# WirelessTransceiverUSB_Rev-.net
KiCad netlist of a schematic drawn in EAGLE
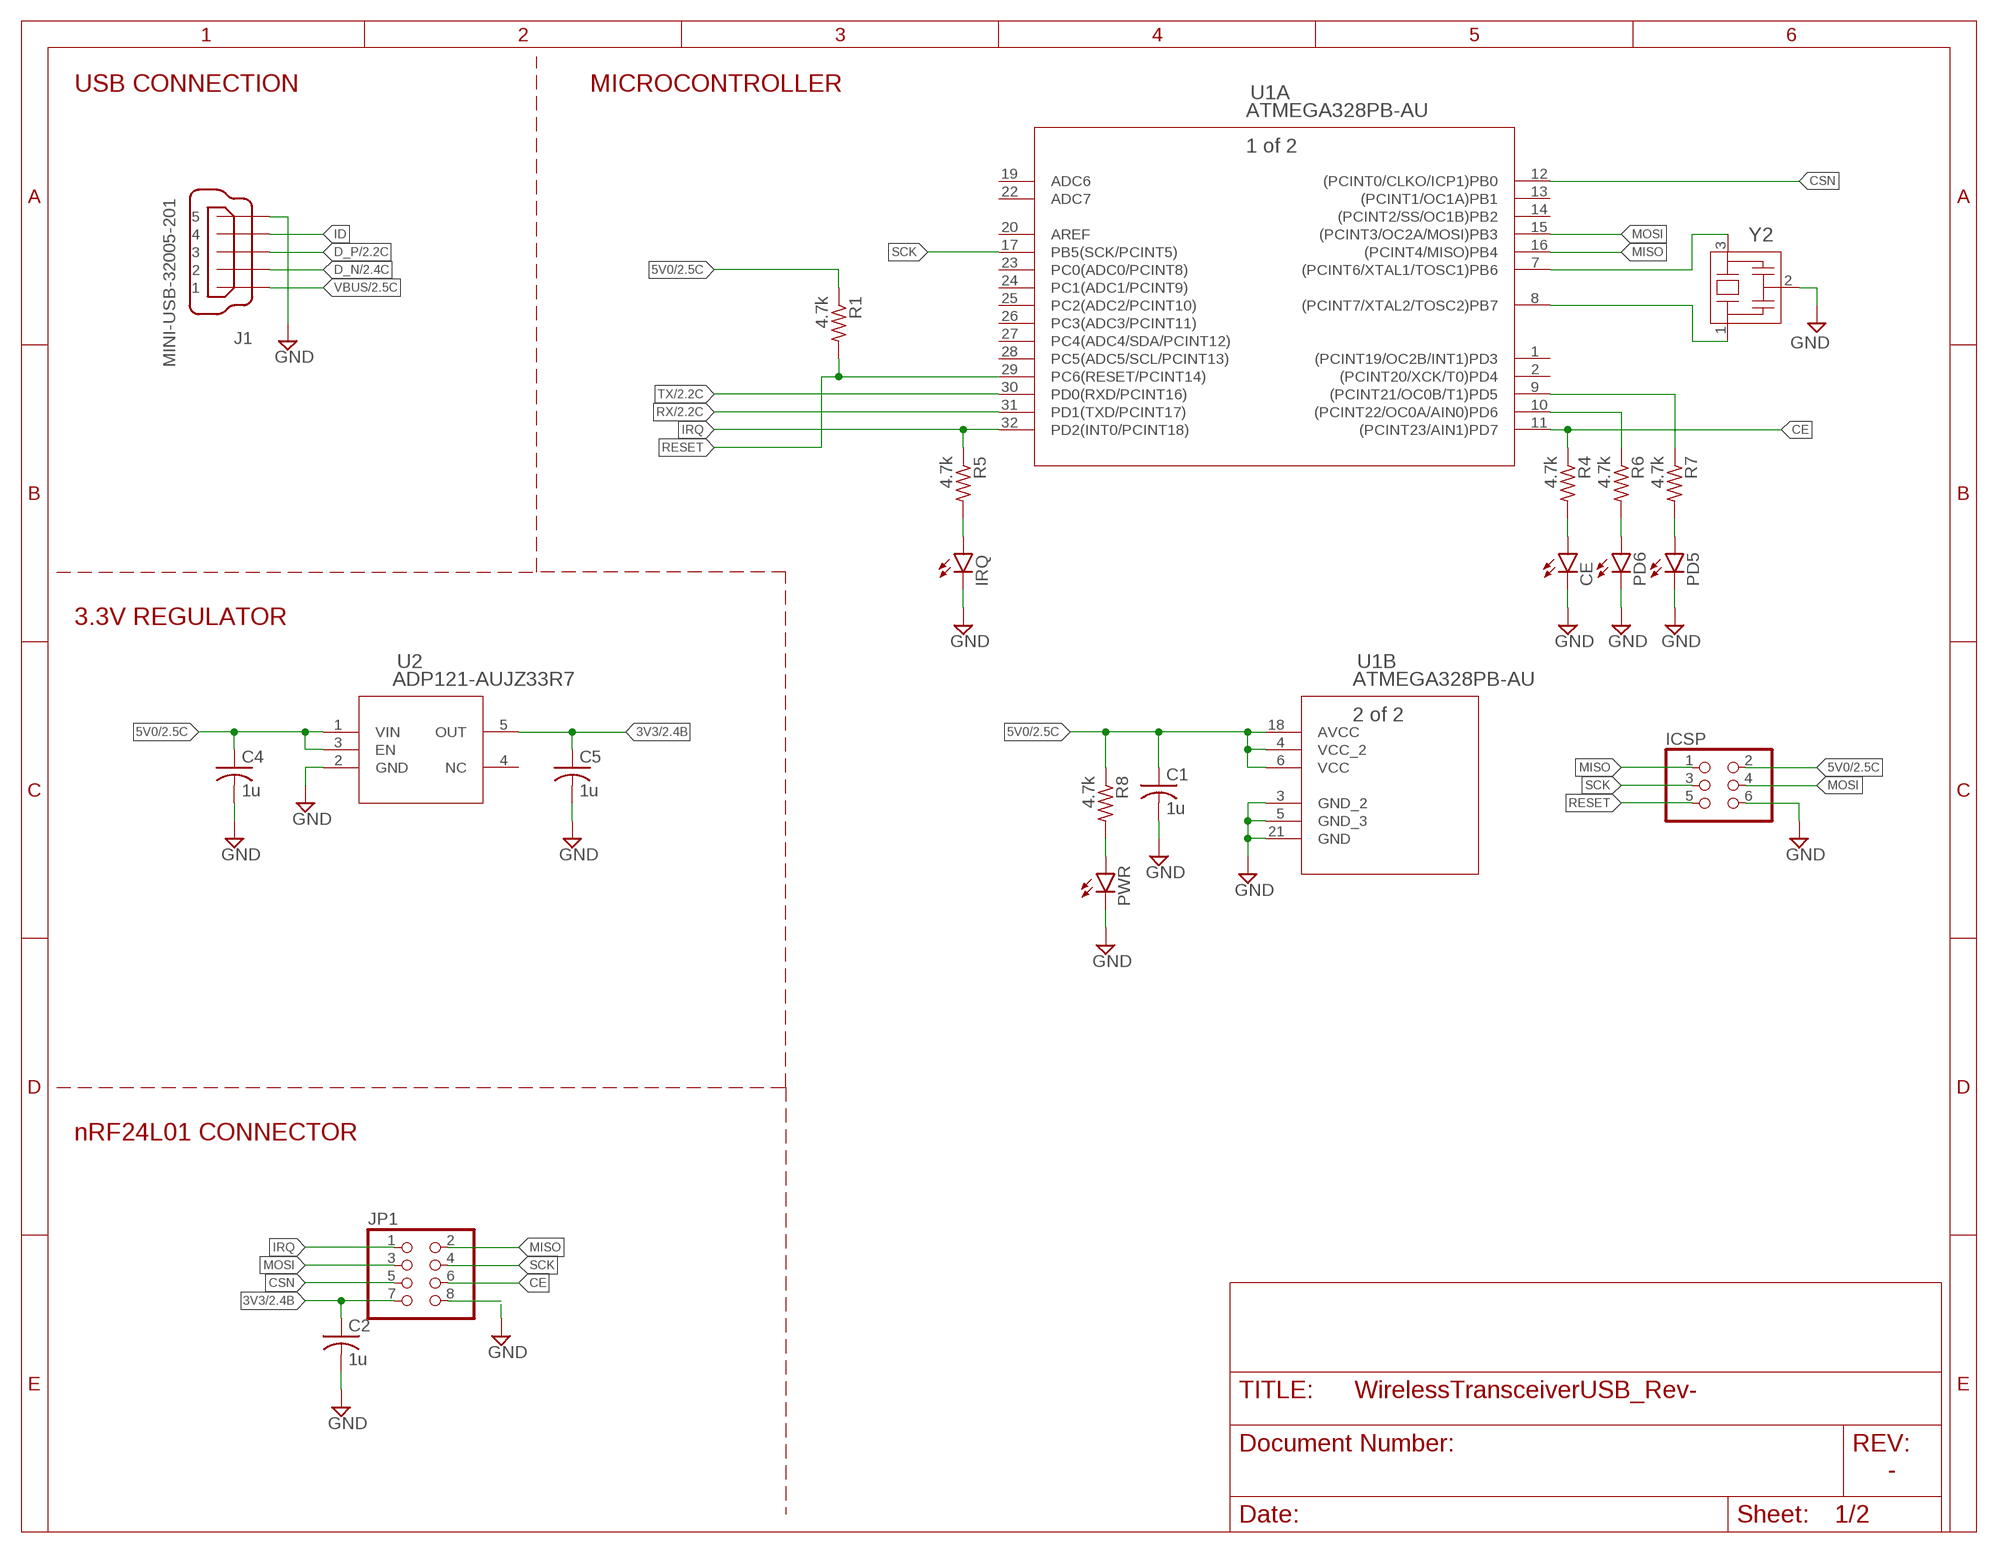
[diagram p0: schematic, sheet 1]
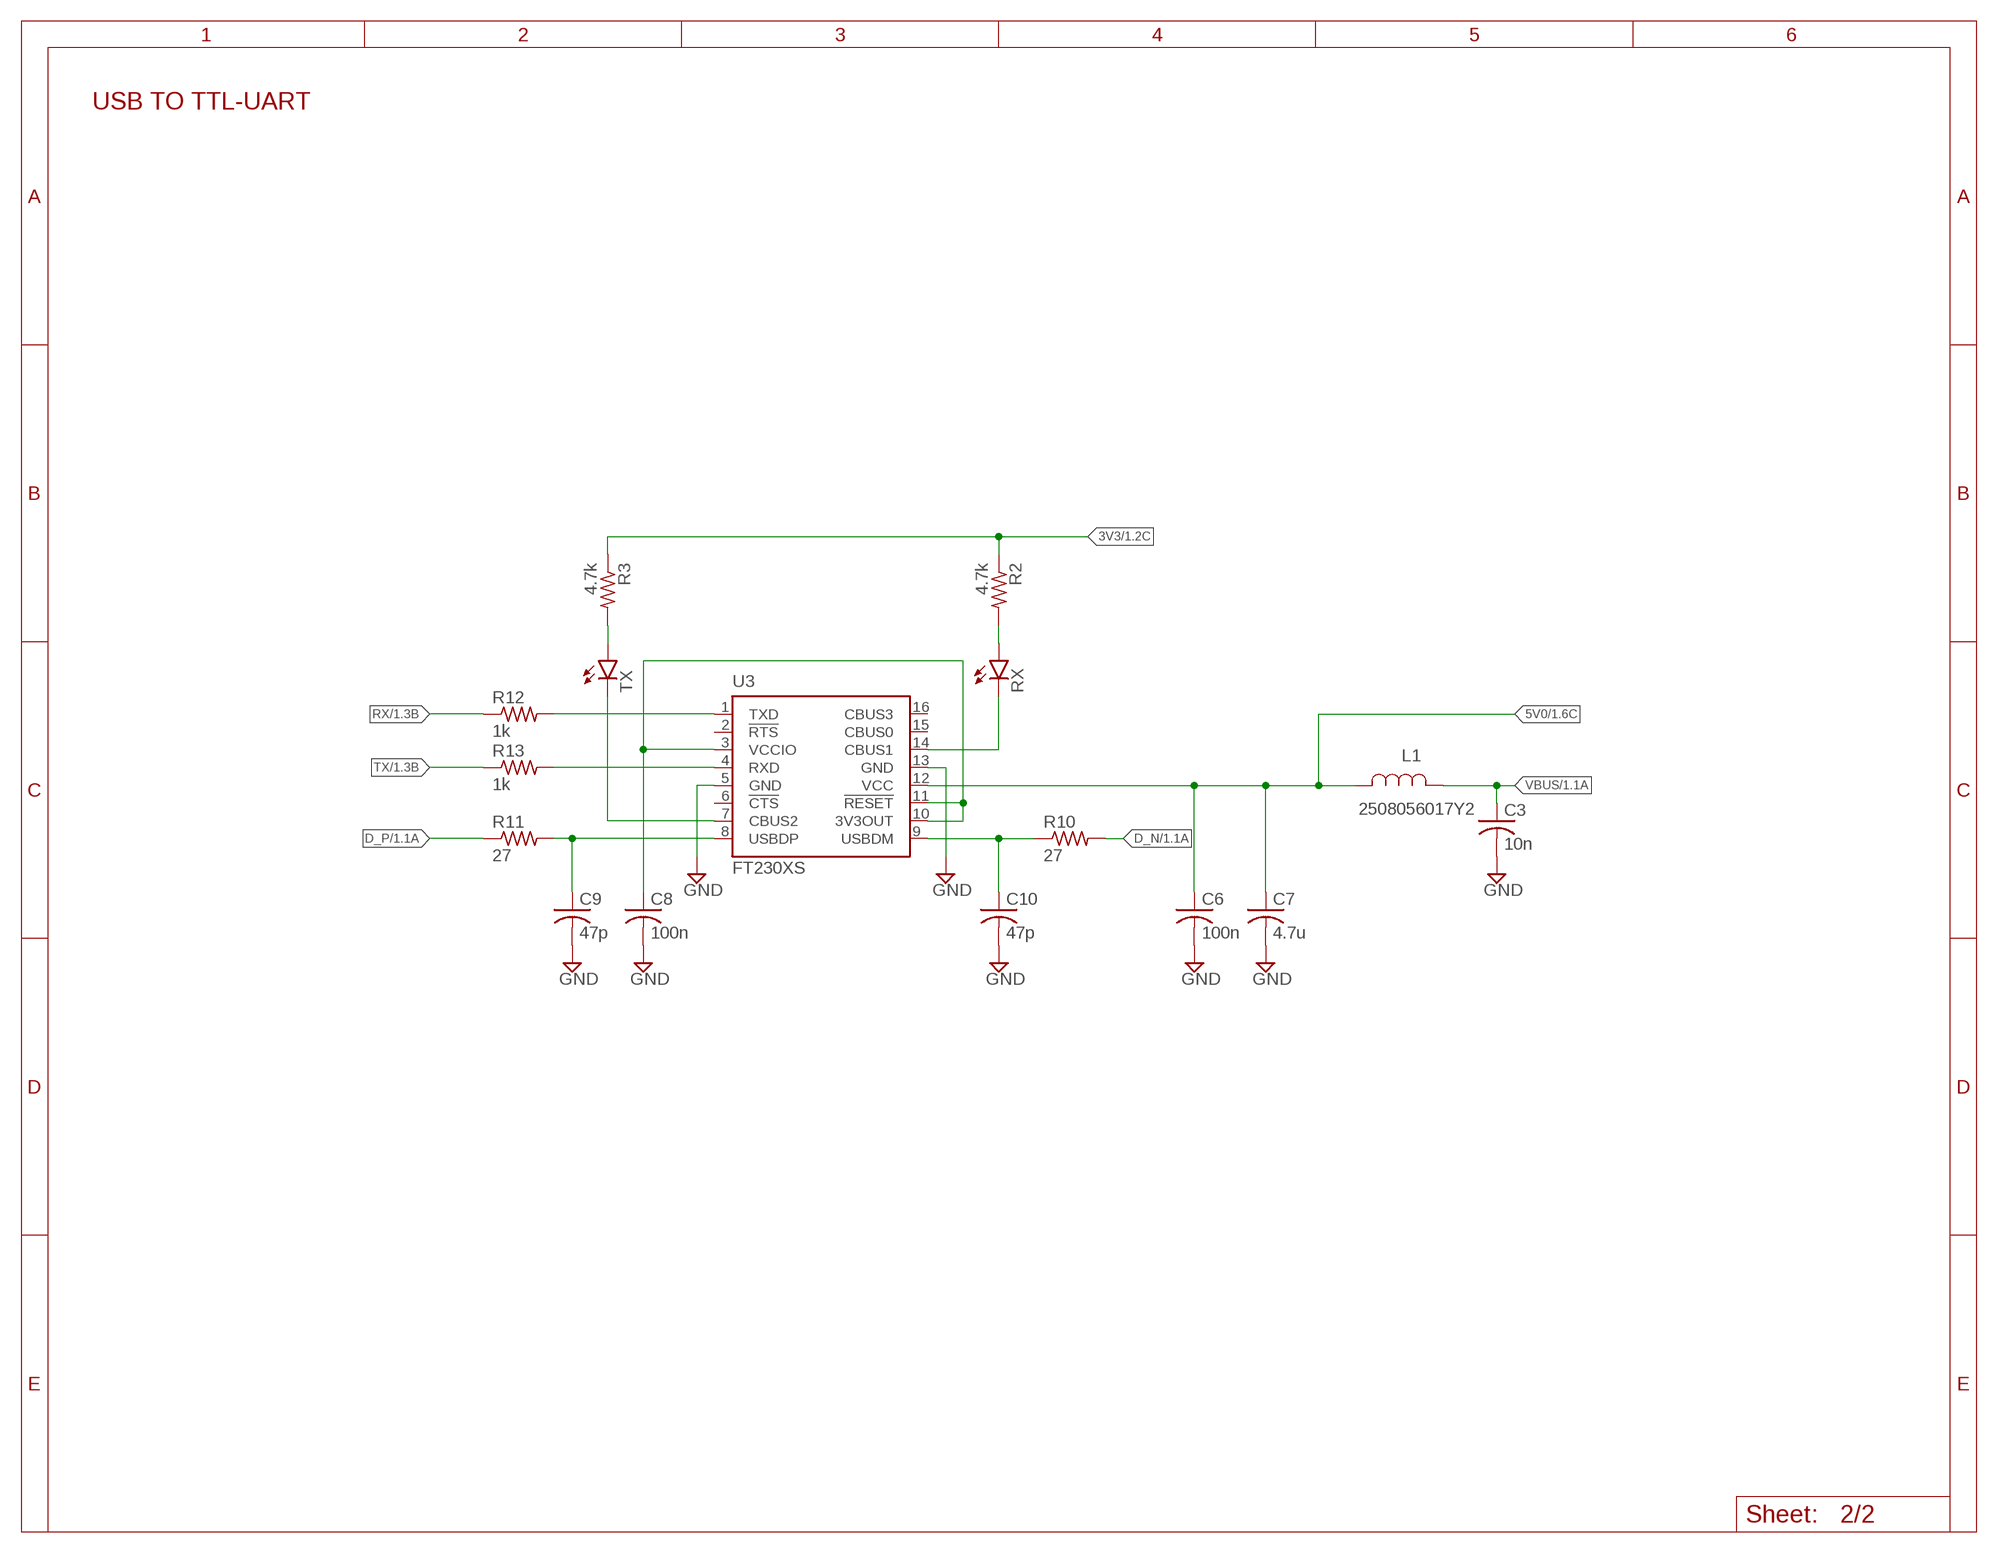
[diagram p1: schematic, sheet 2]

(export (version "E")
  (design (tool "Eeschema 10.0.6"))
  (components
    (comp (ref "C1")
      (value "1u")
      (footprint "eagle-import:C0805")
      (libsource (lib "eagle-import") (part "C-USC0805"))
    )
    (comp (ref "C2")
      (value "1u")
      (footprint "eagle-import:C0805")
      (libsource (lib "eagle-import") (part "C-USC0805"))
    )
    (comp (ref "C4")
      (value "1u")
      (footprint "eagle-import:C0805")
      (libsource (lib "eagle-import") (part "C-USC0805"))
    )
    (comp (ref "C5")
      (value "1u")
      (footprint "eagle-import:C0805")
      (libsource (lib "eagle-import") (part "C-USC0805"))
    )
    (comp (ref "CE")
      (value "LEDSML0805")
      (footprint "eagle-import:SML0805")
      (libsource (lib "eagle-import") (part "LEDSML0805"))
    )
    (comp (ref "ICSP")
      (value "PINHD-2X3")
      (footprint "eagle-import:2X03")
      (libsource (lib "eagle-import") (part "PINHD-2X3"))
    )
    (comp (ref "IRQ")
      (value "LEDSML0805")
      (footprint "eagle-import:SML0805")
      (libsource (lib "eagle-import") (part "LEDSML0805"))
    )
    (comp (ref "J1")
      (value "MINI-USB-32005-201")
      (footprint "eagle-import:32005-201")
      (libsource (lib "eagle-import") (part "MINI-USB-32005-201"))
    )
    (comp (ref "JP1")
      (value "PINHD-2X4")
      (footprint "eagle-import:2X04")
      (libsource (lib "eagle-import") (part "PINHD-2X4"))
    )
    (comp (ref "PD5")
      (value "LEDSML0805")
      (footprint "eagle-import:SML0805")
      (libsource (lib "eagle-import") (part "LEDSML0805"))
    )
    (comp (ref "PD6")
      (value "LEDSML0805")
      (footprint "eagle-import:SML0805")
      (libsource (lib "eagle-import") (part "LEDSML0805"))
    )
    (comp (ref "PWR")
      (value "LEDSML0805")
      (footprint "eagle-import:SML0805")
      (libsource (lib "eagle-import") (part "LEDSML0805"))
    )
    (comp (ref "R1")
      (value "4.7k")
      (footprint "eagle-import:R0805")
      (libsource (lib "eagle-import") (part "R-US_R0805"))
    )
    (comp (ref "R4")
      (value "4.7k")
      (footprint "eagle-import:R0805")
      (libsource (lib "eagle-import") (part "R-US_R0805"))
    )
    (comp (ref "R5")
      (value "4.7k")
      (footprint "eagle-import:R0805")
      (libsource (lib "eagle-import") (part "R-US_R0805"))
    )
    (comp (ref "R6")
      (value "4.7k")
      (footprint "eagle-import:R0805")
      (libsource (lib "eagle-import") (part "R-US_R0805"))
    )
    (comp (ref "R7")
      (value "4.7k")
      (footprint "eagle-import:R0805")
      (libsource (lib "eagle-import") (part "R-US_R0805"))
    )
    (comp (ref "R8")
      (value "4.7k")
      (footprint "eagle-import:R0805")
      (libsource (lib "eagle-import") (part "R-US_R0805"))
    )
    (comp (ref "U1")
      (value "ATMEGA328PB-AU")
      (footprint "eagle-import:32A_MCH")
      (fields (field (name "COPYRIGHT") "Copyright (C) 2023 Ultra Librarian. All rights reserved."))
      (libsource (lib "eagle-import") (part "ATMEGA328PB-AU"))
    )
    (comp (ref "U2")
      (value "ADP121-AUJZ33R7")
      (footprint "eagle-import:UJ_5_ADI")
      (fields (field (name "COPYRIGHT") "Copyright (C) 2023 Ultra Librarian. All rights reserved."))
      (libsource (lib "eagle-import") (part "ADP121-AUJZ33R7"))
    )
    (comp (ref "Y2")
      (value "CSTNE16M0V530000R0")
      (footprint "eagle-import:CSTNE16M0V530000R0_MUR")
      (fields (field (name "COPYRIGHT") "Copyright (C) 2023 Ultra Librarian. All rights reserved."))
      (libsource (lib "eagle-import") (part "CSTNE16M0V530000R0"))
    )
    (comp (ref "C3")
      (value "10n")
      (footprint "eagle-import:C0805")
      (libsource (lib "eagle-import") (part "C-USC0805"))
    )
    (comp (ref "C6")
      (value "100n")
      (footprint "eagle-import:C0805")
      (libsource (lib "eagle-import") (part "C-USC0805"))
    )
    (comp (ref "C7")
      (value "4.7u")
      (footprint "eagle-import:C0805")
      (libsource (lib "eagle-import") (part "C-USC0805"))
    )
    (comp (ref "C8")
      (value "100n")
      (footprint "eagle-import:C0805")
      (libsource (lib "eagle-import") (part "C-USC0805"))
    )
    (comp (ref "C9")
      (value "47p")
      (footprint "eagle-import:C0603")
      (libsource (lib "eagle-import") (part "C-USC0603"))
    )
    (comp (ref "C10")
      (value "47p")
      (footprint "eagle-import:C0603")
      (libsource (lib "eagle-import") (part "C-USC0603"))
    )
    (comp (ref "L1")
      (value "2508056017Y2")
      (footprint "eagle-import:IND_25_0805_FRT")
      (fields (field (name "COPYRIGHT") "Copyright (C) 2023 Ultra Librarian. All rights reserved."))
      (libsource (lib "eagle-import") (part "2508056017Y2"))
    )
    (comp (ref "R2")
      (value "4.7k")
      (footprint "eagle-import:R0805")
      (libsource (lib "eagle-import") (part "R-US_R0805"))
    )
    (comp (ref "R3")
      (value "4.7k")
      (footprint "eagle-import:R0805")
      (libsource (lib "eagle-import") (part "R-US_R0805"))
    )
    (comp (ref "R10")
      (value "27")
      (footprint "eagle-import:R0603")
      (libsource (lib "eagle-import") (part "R-US_R0603"))
    )
    (comp (ref "R11")
      (value "27")
      (footprint "eagle-import:R0603")
      (libsource (lib "eagle-import") (part "R-US_R0603"))
    )
    (comp (ref "R12")
      (value "1k")
      (footprint "eagle-import:R0805")
      (libsource (lib "eagle-import") (part "R-US_R0805"))
    )
    (comp (ref "R13")
      (value "1k")
      (footprint "eagle-import:R0805")
      (libsource (lib "eagle-import") (part "R-US_R0805"))
    )
    (comp (ref "RX")
      (value "LEDSML0805")
      (footprint "eagle-import:SML0805")
      (libsource (lib "eagle-import") (part "LEDSML0805"))
    )
    (comp (ref "TX")
      (value "LEDSML0805")
      (footprint "eagle-import:SML0805")
      (libsource (lib "eagle-import") (part "LEDSML0805"))
    )
    (comp (ref "U3")
      (value "FT230XS")
      (footprint "eagle-import:SSOP16")
      (libsource (lib "eagle-import") (part "FT230XS"))
    )
  )
  (nets
    (net (code "1") (name "3V3") (class "Default")
      (node (ref "C2") (pin "1") (pinfunction "1_1") (pintype "passive"))
      (node (ref "C5") (pin "1") (pinfunction "1_1") (pintype "passive"))
      (node (ref "JP1") (pin "7") (pinfunction "7_7") (pintype "passive"))
      (node (ref "R2") (pin "1") (pinfunction "1_1") (pintype "passive"))
      (node (ref "R3") (pin "1") (pinfunction "1_1") (pintype "passive"))
      (node (ref "U2") (pin "5") (pinfunction "OUT_5") (pintype "output"))
    )
    (net (code "2") (name "5V0") (class "Default")
      (node (ref "C1") (pin "1") (pinfunction "1_1") (pintype "passive"))
      (node (ref "C4") (pin "1") (pinfunction "1_1") (pintype "passive"))
      (node (ref "C6") (pin "1") (pinfunction "1_1") (pintype "passive"))
      (node (ref "C7") (pin "1") (pinfunction "1_1") (pintype "passive"))
      (node (ref "ICSP") (pin "2") (pinfunction "2_2") (pintype "passive"))
      (node (ref "L1") (pin "2") (pinfunction "2_2") (pintype "passive"))
      (node (ref "R1") (pin "1") (pinfunction "1_1") (pintype "passive"))
      (node (ref "R8") (pin "1") (pinfunction "1_1") (pintype "passive"))
      (node (ref "U1") (pin "18") (pinfunction "AVCC_18") (pintype "power_in"))
      (node (ref "U1") (pin "4") (pinfunction "VCC_2_4") (pintype "power_in"))
      (node (ref "U1") (pin "6") (pinfunction "VCC_6") (pintype "power_in"))
      (node (ref "U2") (pin "1") (pinfunction "VIN_1") (pintype "input"))
      (node (ref "U2") (pin "3") (pinfunction "EN_3") (pintype "input"))
      (node (ref "U3") (pin "12") (pinfunction "VCC_12") (pintype "power_in"))
    )
    (net (code "3") (name "CE") (class "Default")
      (node (ref "JP1") (pin "6") (pinfunction "6_6") (pintype "passive"))
      (node (ref "R4") (pin "1") (pinfunction "1_1") (pintype "passive"))
      (node (ref "U1") (pin "11") (pinfunction "(PCINT23/AIN1)PD7_11") (pintype "bidirectional"))
    )
    (net (code "4") (name "CSN") (class "Default")
      (node (ref "JP1") (pin "5") (pinfunction "5_5") (pintype "passive"))
      (node (ref "U1") (pin "12") (pinfunction "(PCINT0/CLKO/ICP1)PB0_12") (pintype "bidirectional"))
    )
    (net (code "5") (name "D_N") (class "Default")
      (node (ref "J1") (pin "2") (pinfunction "2_2") (pintype "passive"))
      (node (ref "R10") (pin "2") (pinfunction "2_2") (pintype "passive"))
    )
    (net (code "6") (name "D_P") (class "Default")
      (node (ref "J1") (pin "3") (pinfunction "3_3") (pintype "passive"))
      (node (ref "R11") (pin "1") (pinfunction "1_1") (pintype "passive"))
    )
    (net (code "7") (name "GND") (class "Default")
      (node (ref "C1") (pin "2") (pinfunction "2_2") (pintype "passive"))
      (node (ref "C10") (pin "2") (pinfunction "2_2") (pintype "passive"))
      (node (ref "C2") (pin "2") (pinfunction "2_2") (pintype "passive"))
      (node (ref "C3") (pin "2") (pinfunction "2_2") (pintype "passive"))
      (node (ref "C4") (pin "2") (pinfunction "2_2") (pintype "passive"))
      (node (ref "C5") (pin "2") (pinfunction "2_2") (pintype "passive"))
      (node (ref "C6") (pin "2") (pinfunction "2_2") (pintype "passive"))
      (node (ref "C7") (pin "2") (pinfunction "2_2") (pintype "passive"))
      (node (ref "C8") (pin "2") (pinfunction "2_2") (pintype "passive"))
      (node (ref "C9") (pin "2") (pinfunction "2_2") (pintype "passive"))
      (node (ref "CE") (pin "C") (pinfunction "C_C") (pintype "passive"))
      (node (ref "ICSP") (pin "6") (pinfunction "6_6") (pintype "passive"))
      (node (ref "IRQ") (pin "C") (pinfunction "C_C") (pintype "passive"))
      (node (ref "J1") (pin "5") (pinfunction "5_5") (pintype "passive"))
      (node (ref "JP1") (pin "8") (pinfunction "8_8") (pintype "passive"))
      (node (ref "PD5") (pin "C") (pinfunction "C_C") (pintype "passive"))
      (node (ref "PD6") (pin "C") (pinfunction "C_C") (pintype "passive"))
      (node (ref "PWR") (pin "C") (pinfunction "C_C") (pintype "passive"))
      (node (ref "U1") (pin "21") (pinfunction "GND_21") (pintype "power_in"))
      (node (ref "U1") (pin "3") (pinfunction "GND_2_3") (pintype "power_in"))
      (node (ref "U1") (pin "5") (pinfunction "GND_3_5") (pintype "power_in"))
      (node (ref "U2") (pin "2") (pinfunction "GND_2") (pintype "power_in"))
      (node (ref "U3") (pin "13") (pinfunction "GND_13") (pintype "power_in"))
      (node (ref "U3") (pin "5") (pinfunction "GND_5") (pintype "power_in"))
      (node (ref "Y2") (pin "2") (pinfunction "2_2") (pintype "passive"))
    )
    (net (code "8") (name "ID") (class "Default")
      (node (ref "J1") (pin "4") (pinfunction "4_4") (pintype "passive"))
    )
    (net (code "9") (name "IRQ") (class "Default")
      (node (ref "JP1") (pin "1") (pinfunction "1_1") (pintype "passive"))
      (node (ref "R5") (pin "1") (pinfunction "1_1") (pintype "passive"))
      (node (ref "U1") (pin "32") (pinfunction "PD2(INT0/PCINT18)_32") (pintype "bidirectional"))
    )
    (net (code "10") (name "MISO") (class "Default")
      (node (ref "ICSP") (pin "1") (pinfunction "1_1") (pintype "passive"))
      (node (ref "JP1") (pin "2") (pinfunction "2_2") (pintype "passive"))
      (node (ref "U1") (pin "16") (pinfunction "(PCINT4/MISO)PB4_16") (pintype "bidirectional"))
    )
    (net (code "11") (name "MOSI") (class "Default")
      (node (ref "ICSP") (pin "4") (pinfunction "4_4") (pintype "passive"))
      (node (ref "JP1") (pin "3") (pinfunction "3_3") (pintype "passive"))
      (node (ref "U1") (pin "15") (pinfunction "(PCINT3/OC2A/MOSI)PB3_15") (pintype "bidirectional"))
    )
    (net (code "12") (name "Net-(CE-PadA)") (class "Default")
      (node (ref "CE") (pin "A") (pinfunction "A_A") (pintype "passive"))
      (node (ref "R4") (pin "2") (pinfunction "2_2") (pintype "passive"))
    )
    (net (code "13") (name "Net-(IRQ-PadA)") (class "Default")
      (node (ref "IRQ") (pin "A") (pinfunction "A_A") (pintype "passive"))
      (node (ref "R5") (pin "2") (pinfunction "2_2") (pintype "passive"))
    )
    (net (code "14") (name "Net-(PD5-PadA)") (class "Default")
      (node (ref "PD5") (pin "A") (pinfunction "A_A") (pintype "passive"))
      (node (ref "R7") (pin "2") (pinfunction "2_2") (pintype "passive"))
    )
    (net (code "15") (name "Net-(PD6-PadA)") (class "Default")
      (node (ref "PD6") (pin "A") (pinfunction "A_A") (pintype "passive"))
      (node (ref "R6") (pin "2") (pinfunction "2_2") (pintype "passive"))
    )
    (net (code "16") (name "Net-(PWR-PadA)") (class "Default")
      (node (ref "PWR") (pin "A") (pinfunction "A_A") (pintype "passive"))
      (node (ref "R8") (pin "2") (pinfunction "2_2") (pintype "passive"))
    )
    (net (code "17") (name "Net-(R2-Pad2)") (class "Default")
      (node (ref "R2") (pin "2") (pinfunction "2_2") (pintype "passive"))
      (node (ref "RX") (pin "A") (pinfunction "A_A") (pintype "passive"))
    )
    (net (code "18") (name "Net-(R3-Pad2)") (class "Default")
      (node (ref "R3") (pin "2") (pinfunction "2_2") (pintype "passive"))
      (node (ref "TX") (pin "A") (pinfunction "A_A") (pintype "passive"))
    )
    (net (code "19") (name "Net-(U1A-(PCINT6{slash}XTAL1{slash}TOSC1)PB6)") (class "Default")
      (node (ref "U1") (pin "7") (pinfunction "(PCINT6/XTAL1/TOSC1)PB6_7") (pintype "bidirectional"))
      (node (ref "Y2") (pin "3") (pinfunction "3_3") (pintype "output"))
    )
    (net (code "20") (name "Net-(U1A-(PCINT7{slash}XTAL2{slash}TOSC2)PB7)") (class "Default")
      (node (ref "U1") (pin "8") (pinfunction "(PCINT7/XTAL2/TOSC2)PB7_8") (pintype "bidirectional"))
      (node (ref "Y2") (pin "1") (pinfunction "1_1") (pintype "input"))
    )
    (net (code "21") (name "Net-(U1A-(PCINT21{slash}OC0B{slash}T1)PD5)") (class "Default")
      (node (ref "R7") (pin "1") (pinfunction "1_1") (pintype "passive"))
      (node (ref "U1") (pin "9") (pinfunction "(PCINT21/OC0B/T1)PD5_9") (pintype "bidirectional"))
    )
    (net (code "22") (name "Net-(U1A-(PCINT22{slash}OC0A{slash}AIN0)PD6)") (class "Default")
      (node (ref "R6") (pin "1") (pinfunction "1_1") (pintype "passive"))
      (node (ref "U1") (pin "10") (pinfunction "(PCINT22/OC0A/AIN0)PD6_10") (pintype "bidirectional"))
    )
    (net (code "23") (name "Net-(U3-3V3OUT)") (class "Default")
      (node (ref "C8") (pin "1") (pinfunction "1_1") (pintype "passive"))
      (node (ref "U3") (pin "10") (pinfunction "3V3OUT_10") (pintype "output"))
      (node (ref "U3") (pin "11") (pinfunction "~{RESET}_11") (pintype "input"))
      (node (ref "U3") (pin "3") (pinfunction "VCCIO_3") (pintype "power_in"))
    )
    (net (code "24") (name "Net-(U3-CBUS1)") (class "Default")
      (node (ref "RX") (pin "C") (pinfunction "C_C") (pintype "passive"))
      (node (ref "U3") (pin "14") (pinfunction "CBUS1_14") (pintype "bidirectional"))
    )
    (net (code "25") (name "Net-(U3-CBUS2)") (class "Default")
      (node (ref "TX") (pin "C") (pinfunction "C_C") (pintype "passive"))
      (node (ref "U3") (pin "7") (pinfunction "CBUS2_7") (pintype "bidirectional"))
    )
    (net (code "26") (name "Net-(U3-RXD)") (class "Default")
      (node (ref "R13") (pin "2") (pinfunction "2_2") (pintype "passive"))
      (node (ref "U3") (pin "4") (pinfunction "RXD_4") (pintype "input"))
    )
    (net (code "27") (name "Net-(U3-TXD)") (class "Default")
      (node (ref "R12") (pin "2") (pinfunction "2_2") (pintype "passive"))
      (node (ref "U3") (pin "1") (pinfunction "TXD_1") (pintype "output"))
    )
    (net (code "28") (name "Net-(U3-USBDM)") (class "Default")
      (node (ref "C10") (pin "1") (pinfunction "1_1") (pintype "passive"))
      (node (ref "R10") (pin "1") (pinfunction "1_1") (pintype "passive"))
      (node (ref "U3") (pin "9") (pinfunction "USBDM_9") (pintype "input"))
    )
    (net (code "29") (name "Net-(U3-USBDP)") (class "Default")
      (node (ref "C9") (pin "1") (pinfunction "1_1") (pintype "passive"))
      (node (ref "R11") (pin "2") (pinfunction "2_2") (pintype "passive"))
      (node (ref "U3") (pin "8") (pinfunction "USBDP_8") (pintype "input"))
    )
    (net (code "30") (name "RESET") (class "Default")
      (node (ref "ICSP") (pin "5") (pinfunction "5_5") (pintype "passive"))
      (node (ref "R1") (pin "2") (pinfunction "2_2") (pintype "passive"))
      (node (ref "U1") (pin "29") (pinfunction "PC6(RESET/PCINT14)_29") (pintype "bidirectional"))
    )
    (net (code "31") (name "RX") (class "Default")
      (node (ref "R12") (pin "1") (pinfunction "1_1") (pintype "passive"))
      (node (ref "U1") (pin "31") (pinfunction "PD1(TXD/PCINT17)_31") (pintype "bidirectional"))
    )
    (net (code "32") (name "SCK") (class "Default")
      (node (ref "ICSP") (pin "3") (pinfunction "3_3") (pintype "passive"))
      (node (ref "JP1") (pin "4") (pinfunction "4_4") (pintype "passive"))
      (node (ref "U1") (pin "17") (pinfunction "PB5(SCK/PCINT5)_17") (pintype "bidirectional"))
    )
    (net (code "33") (name "TX") (class "Default")
      (node (ref "R13") (pin "1") (pinfunction "1_1") (pintype "passive"))
      (node (ref "U1") (pin "30") (pinfunction "PD0(RXD/PCINT16)_30") (pintype "bidirectional"))
    )
    (net (code "34") (name "VBUS") (class "Default")
      (node (ref "C3") (pin "1") (pinfunction "1_1") (pintype "passive"))
      (node (ref "J1") (pin "1") (pinfunction "1_1") (pintype "passive"))
      (node (ref "L1") (pin "1") (pinfunction "1_1") (pintype "passive"))
    )
    (net (code "35") (name "unconnected-(U1A-(PCINT1{slash}OC1A)PB1-Pad13)") (class "Default")
      (node (ref "U1") (pin "13") (pinfunction "(PCINT1/OC1A)PB1_13") (pintype "bidirectional"))
    )
    (net (code "36") (name "unconnected-(U1A-(PCINT2{slash}SS{slash}OC1B)PB2-Pad14)") (class "Default")
      (node (ref "U1") (pin "14") (pinfunction "(PCINT2/SS/OC1B)PB2_14") (pintype "bidirectional"))
    )
    (net (code "37") (name "unconnected-(U1A-(PCINT19{slash}OC2B{slash}INT1)PD3-Pad1)") (class "Default")
      (node (ref "U1") (pin "1") (pinfunction "(PCINT19/OC2B/INT1)PD3_1") (pintype "bidirectional"))
    )
    (net (code "38") (name "unconnected-(U1A-(PCINT20{slash}XCK{slash}T0)PD4-Pad2)") (class "Default")
      (node (ref "U1") (pin "2") (pinfunction "(PCINT20/XCK/T0)PD4_2") (pintype "bidirectional"))
    )
    (net (code "39") (name "unconnected-(U1A-ADC6-Pad19)") (class "Default")
      (node (ref "U1") (pin "19") (pinfunction "ADC6_19") (pintype "input"))
    )
    (net (code "40") (name "unconnected-(U1A-ADC7-Pad22)") (class "Default")
      (node (ref "U1") (pin "22") (pinfunction "ADC7_22") (pintype "input"))
    )
    (net (code "41") (name "unconnected-(U1A-AREF-Pad20)") (class "Default")
      (node (ref "U1") (pin "20") (pinfunction "AREF_20") (pintype "passive"))
    )
    (net (code "42") (name "unconnected-(U1A-PC0(ADC0{slash}PCINT8)-Pad23)") (class "Default")
      (node (ref "U1") (pin "23") (pinfunction "PC0(ADC0/PCINT8)_23") (pintype "bidirectional"))
    )
    (net (code "43") (name "unconnected-(U1A-PC1(ADC1{slash}PCINT9)-Pad24)") (class "Default")
      (node (ref "U1") (pin "24") (pinfunction "PC1(ADC1/PCINT9)_24") (pintype "bidirectional"))
    )
    (net (code "44") (name "unconnected-(U1A-PC2(ADC2{slash}PCINT10)-Pad25)") (class "Default")
      (node (ref "U1") (pin "25") (pinfunction "PC2(ADC2/PCINT10)_25") (pintype "bidirectional"))
    )
    (net (code "45") (name "unconnected-(U1A-PC3(ADC3{slash}PCINT11)-Pad26)") (class "Default")
      (node (ref "U1") (pin "26") (pinfunction "PC3(ADC3/PCINT11)_26") (pintype "bidirectional"))
    )
    (net (code "46") (name "unconnected-(U1A-PC4(ADC4{slash}SDA{slash}PCINT12)-Pad27)") (class "Default")
      (node (ref "U1") (pin "27") (pinfunction "PC4(ADC4/SDA/PCINT12)_27") (pintype "bidirectional"))
    )
    (net (code "47") (name "unconnected-(U1A-PC5(ADC5{slash}SCL{slash}PCINT13)-Pad28)") (class "Default")
      (node (ref "U1") (pin "28") (pinfunction "PC5(ADC5/SCL/PCINT13)_28") (pintype "bidirectional"))
    )
    (net (code "48") (name "unconnected-(U2-NC-Pad4)") (class "Default")
      (node (ref "U2") (pin "4") (pinfunction "NC_4") (pintype "no_connect"))
    )
    (net (code "49") (name "unconnected-(U3-CBUS0-Pad15)") (class "Default")
      (node (ref "U3") (pin "15") (pinfunction "CBUS0_15") (pintype "bidirectional"))
    )
    (net (code "50") (name "unconnected-(U3-CBUS3-Pad16)") (class "Default")
      (node (ref "U3") (pin "16") (pinfunction "CBUS3_16") (pintype "bidirectional"))
    )
    (net (code "51") (name "unconnected-(U3-~{CTS}-Pad6)") (class "Default")
      (node (ref "U3") (pin "6") (pinfunction "~{CTS}_6") (pintype "input"))
    )
    (net (code "52") (name "unconnected-(U3-~{RTS}-Pad2)") (class "Default")
      (node (ref "U3") (pin "2") (pinfunction "~{RTS}_2") (pintype "output"))
    )
  )
)
